# Sensor.net
KiCad netlist of a schematic drawn in EAGLE
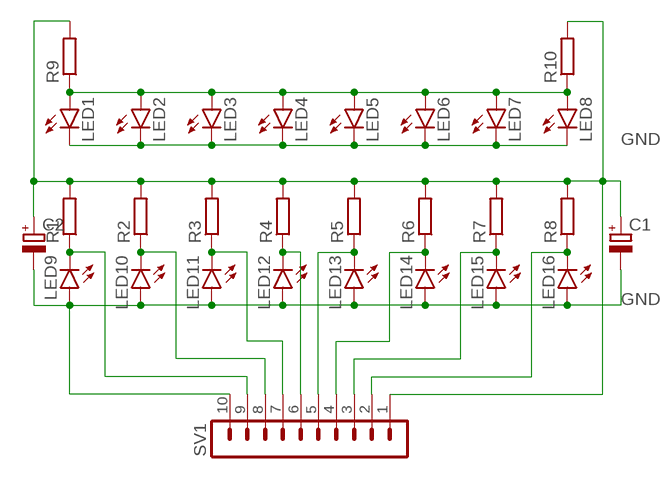
[diagram p0: schematic, sheet 1]

(export (version "E")
  (design (tool "Eeschema 10.0.6"))
  (components
    (comp (ref "C1")
      (value "CPOL-EUE2-4")
      (footprint "eagle-import:E2-4")
      (libsource (lib "eagle-import") (part "CPOL-EUE2-4"))
    )
    (comp (ref "C2")
      (value "CPOL-EUE2-4")
      (footprint "eagle-import:E2-4")
      (libsource (lib "eagle-import") (part "CPOL-EUE2-4"))
    )
    (comp (ref "LED1")
      (value "LED5MM")
      (footprint "eagle-import:LED5MM")
      (libsource (lib "eagle-import") (part "LED5MM"))
    )
    (comp (ref "LED2")
      (value "LED5MM")
      (footprint "eagle-import:LED5MM")
      (libsource (lib "eagle-import") (part "LED5MM"))
    )
    (comp (ref "LED3")
      (value "LED5MM")
      (footprint "eagle-import:LED5MM")
      (libsource (lib "eagle-import") (part "LED5MM"))
    )
    (comp (ref "LED4")
      (value "LED5MM")
      (footprint "eagle-import:LED5MM")
      (libsource (lib "eagle-import") (part "LED5MM"))
    )
    (comp (ref "LED5")
      (value "LED5MM")
      (footprint "eagle-import:LED5MM")
      (libsource (lib "eagle-import") (part "LED5MM"))
    )
    (comp (ref "LED6")
      (value "LED5MM")
      (footprint "eagle-import:LED5MM")
      (libsource (lib "eagle-import") (part "LED5MM"))
    )
    (comp (ref "LED7")
      (value "LED5MM")
      (footprint "eagle-import:LED5MM")
      (libsource (lib "eagle-import") (part "LED5MM"))
    )
    (comp (ref "LED8")
      (value "LED5MM")
      (footprint "eagle-import:LED5MM")
      (libsource (lib "eagle-import") (part "LED5MM"))
    )
    (comp (ref "LED9")
      (value "LED5MM")
      (footprint "eagle-import:LED5MM")
      (libsource (lib "eagle-import") (part "LED5MM"))
    )
    (comp (ref "LED10")
      (value "LED5MM")
      (footprint "eagle-import:LED5MM")
      (libsource (lib "eagle-import") (part "LED5MM"))
    )
    (comp (ref "LED11")
      (value "LED5MM")
      (footprint "eagle-import:LED5MM")
      (libsource (lib "eagle-import") (part "LED5MM"))
    )
    (comp (ref "LED12")
      (value "LED5MM")
      (footprint "eagle-import:LED5MM")
      (libsource (lib "eagle-import") (part "LED5MM"))
    )
    (comp (ref "LED13")
      (value "LED5MM")
      (footprint "eagle-import:LED5MM")
      (libsource (lib "eagle-import") (part "LED5MM"))
    )
    (comp (ref "LED14")
      (value "LED5MM")
      (footprint "eagle-import:LED5MM")
      (libsource (lib "eagle-import") (part "LED5MM"))
    )
    (comp (ref "LED15")
      (value "LED5MM")
      (footprint "eagle-import:LED5MM")
      (libsource (lib "eagle-import") (part "LED5MM"))
    )
    (comp (ref "LED16")
      (value "LED5MM")
      (footprint "eagle-import:LED5MM")
      (libsource (lib "eagle-import") (part "LED5MM"))
    )
    (comp (ref "R1")
      (value "R-EU_0309/10")
      (footprint "eagle-import:0309_10")
      (libsource (lib "eagle-import") (part "R-EU_0309/10"))
    )
    (comp (ref "R2")
      (value "R-EU_0309/10")
      (footprint "eagle-import:0309_10")
      (libsource (lib "eagle-import") (part "R-EU_0309/10"))
    )
    (comp (ref "R3")
      (value "R-EU_0309/10")
      (footprint "eagle-import:0309_10")
      (libsource (lib "eagle-import") (part "R-EU_0309/10"))
    )
    (comp (ref "R4")
      (value "R-EU_0309/10")
      (footprint "eagle-import:0309_10")
      (libsource (lib "eagle-import") (part "R-EU_0309/10"))
    )
    (comp (ref "R5")
      (value "R-EU_0309/10")
      (footprint "eagle-import:0309_10")
      (libsource (lib "eagle-import") (part "R-EU_0309/10"))
    )
    (comp (ref "R6")
      (value "R-EU_0309/10")
      (footprint "eagle-import:0309_10")
      (libsource (lib "eagle-import") (part "R-EU_0309/10"))
    )
    (comp (ref "R7")
      (value "R-EU_0309/10")
      (footprint "eagle-import:0309_10")
      (libsource (lib "eagle-import") (part "R-EU_0309/10"))
    )
    (comp (ref "R8")
      (value "R-EU_0309/10")
      (footprint "eagle-import:0309_10")
      (libsource (lib "eagle-import") (part "R-EU_0309/10"))
    )
    (comp (ref "R9")
      (value "R-EU_0309/10")
      (footprint "eagle-import:0309_10")
      (libsource (lib "eagle-import") (part "R-EU_0309/10"))
    )
    (comp (ref "R10")
      (value "R-EU_0309/10")
      (footprint "eagle-import:0309_10")
      (libsource (lib "eagle-import") (part "R-EU_0309/10"))
    )
    (comp (ref "SV1")
      (value "MA10-1")
      (footprint "eagle-import:MA10-1")
      (libsource (lib "eagle-import") (part "MA10-1"))
    )
  )
  (nets
    (net (code "1") (name "/GND") (class "Default")
      (node (ref "C1") (pin "-") (pinfunction "-_-") (pintype "passive"))
      (node (ref "C2") (pin "-") (pinfunction "-_-") (pintype "passive"))
      (node (ref "LED1") (pin "K") (pinfunction "C_K") (pintype "passive"))
      (node (ref "LED10") (pin "A") (pinfunction "A_A") (pintype "passive"))
      (node (ref "LED11") (pin "A") (pinfunction "A_A") (pintype "passive"))
      (node (ref "LED12") (pin "A") (pinfunction "A_A") (pintype "passive"))
      (node (ref "LED13") (pin "A") (pinfunction "A_A") (pintype "passive"))
      (node (ref "LED14") (pin "A") (pinfunction "A_A") (pintype "passive"))
      (node (ref "LED15") (pin "A") (pinfunction "A_A") (pintype "passive"))
      (node (ref "LED16") (pin "A") (pinfunction "A_A") (pintype "passive"))
      (node (ref "LED2") (pin "K") (pinfunction "C_K") (pintype "passive"))
      (node (ref "LED3") (pin "K") (pinfunction "C_K") (pintype "passive"))
      (node (ref "LED4") (pin "K") (pinfunction "C_K") (pintype "passive"))
      (node (ref "LED5") (pin "K") (pinfunction "C_K") (pintype "passive"))
      (node (ref "LED6") (pin "K") (pinfunction "C_K") (pintype "passive"))
      (node (ref "LED7") (pin "K") (pinfunction "C_K") (pintype "passive"))
      (node (ref "LED8") (pin "K") (pinfunction "C_K") (pintype "passive"))
      (node (ref "LED9") (pin "A") (pinfunction "A_A") (pintype "passive"))
      (node (ref "SV1") (pin "10") (pinfunction "10_10") (pintype "passive"))
    )
    (net (code "2") (name "Net-(C1-Pad+)") (class "Default")
      (node (ref "C1") (pin "+") (pinfunction "+_+") (pintype "passive"))
      (node (ref "C2") (pin "+") (pinfunction "+_+") (pintype "passive"))
      (node (ref "R1") (pin "2") (pinfunction "2_2") (pintype "passive"))
      (node (ref "R10") (pin "2") (pinfunction "2_2") (pintype "passive"))
      (node (ref "R2") (pin "2") (pinfunction "2_2") (pintype "passive"))
      (node (ref "R3") (pin "2") (pinfunction "2_2") (pintype "passive"))
      (node (ref "R4") (pin "2") (pinfunction "2_2") (pintype "passive"))
      (node (ref "R5") (pin "2") (pinfunction "2_2") (pintype "passive"))
      (node (ref "R6") (pin "2") (pinfunction "2_2") (pintype "passive"))
      (node (ref "R7") (pin "2") (pinfunction "2_2") (pintype "passive"))
      (node (ref "R8") (pin "2") (pinfunction "2_2") (pintype "passive"))
      (node (ref "R9") (pin "2") (pinfunction "2_2") (pintype "passive"))
      (node (ref "SV1") (pin "1") (pinfunction "1_1") (pintype "passive"))
    )
    (net (code "3") (name "Net-(LED1-PadA)") (class "Default")
      (node (ref "LED1") (pin "A") (pinfunction "A_A") (pintype "passive"))
      (node (ref "LED2") (pin "A") (pinfunction "A_A") (pintype "passive"))
      (node (ref "LED3") (pin "A") (pinfunction "A_A") (pintype "passive"))
      (node (ref "LED4") (pin "A") (pinfunction "A_A") (pintype "passive"))
      (node (ref "LED5") (pin "A") (pinfunction "A_A") (pintype "passive"))
      (node (ref "LED6") (pin "A") (pinfunction "A_A") (pintype "passive"))
      (node (ref "LED7") (pin "A") (pinfunction "A_A") (pintype "passive"))
      (node (ref "LED8") (pin "A") (pinfunction "A_A") (pintype "passive"))
      (node (ref "R10") (pin "1") (pinfunction "1_1") (pintype "passive"))
      (node (ref "R9") (pin "1") (pinfunction "1_1") (pintype "passive"))
    )
    (net (code "4") (name "Net-(LED9-C)") (class "Default")
      (node (ref "LED9") (pin "K") (pinfunction "C_K") (pintype "passive"))
      (node (ref "R1") (pin "1") (pinfunction "1_1") (pintype "passive"))
      (node (ref "SV1") (pin "9") (pinfunction "9_9") (pintype "passive"))
    )
    (net (code "5") (name "Net-(LED10-C)") (class "Default")
      (node (ref "LED10") (pin "K") (pinfunction "C_K") (pintype "passive"))
      (node (ref "R2") (pin "1") (pinfunction "1_1") (pintype "passive"))
      (node (ref "SV1") (pin "8") (pinfunction "8_8") (pintype "passive"))
    )
    (net (code "6") (name "Net-(LED11-C)") (class "Default")
      (node (ref "LED11") (pin "K") (pinfunction "C_K") (pintype "passive"))
      (node (ref "R3") (pin "1") (pinfunction "1_1") (pintype "passive"))
      (node (ref "SV1") (pin "7") (pinfunction "7_7") (pintype "passive"))
    )
    (net (code "7") (name "Net-(LED12-C)") (class "Default")
      (node (ref "LED12") (pin "K") (pinfunction "C_K") (pintype "passive"))
      (node (ref "R4") (pin "1") (pinfunction "1_1") (pintype "passive"))
      (node (ref "SV1") (pin "6") (pinfunction "6_6") (pintype "passive"))
    )
    (net (code "8") (name "Net-(LED13-C)") (class "Default")
      (node (ref "LED13") (pin "K") (pinfunction "C_K") (pintype "passive"))
      (node (ref "R5") (pin "1") (pinfunction "1_1") (pintype "passive"))
      (node (ref "SV1") (pin "5") (pinfunction "5_5") (pintype "passive"))
    )
    (net (code "9") (name "Net-(LED14-C)") (class "Default")
      (node (ref "LED14") (pin "K") (pinfunction "C_K") (pintype "passive"))
      (node (ref "R6") (pin "1") (pinfunction "1_1") (pintype "passive"))
      (node (ref "SV1") (pin "4") (pinfunction "4_4") (pintype "passive"))
    )
    (net (code "10") (name "Net-(LED15-C)") (class "Default")
      (node (ref "LED15") (pin "K") (pinfunction "C_K") (pintype "passive"))
      (node (ref "R7") (pin "1") (pinfunction "1_1") (pintype "passive"))
      (node (ref "SV1") (pin "3") (pinfunction "3_3") (pintype "passive"))
    )
    (net (code "11") (name "Net-(LED16-C)") (class "Default")
      (node (ref "LED16") (pin "K") (pinfunction "C_K") (pintype "passive"))
      (node (ref "R8") (pin "1") (pinfunction "1_1") (pintype "passive"))
      (node (ref "SV1") (pin "2") (pinfunction "2_2") (pintype "passive"))
    )
  )
)
